# schematic.net
KiCad netlist of a schematic drawn in Altium Designer
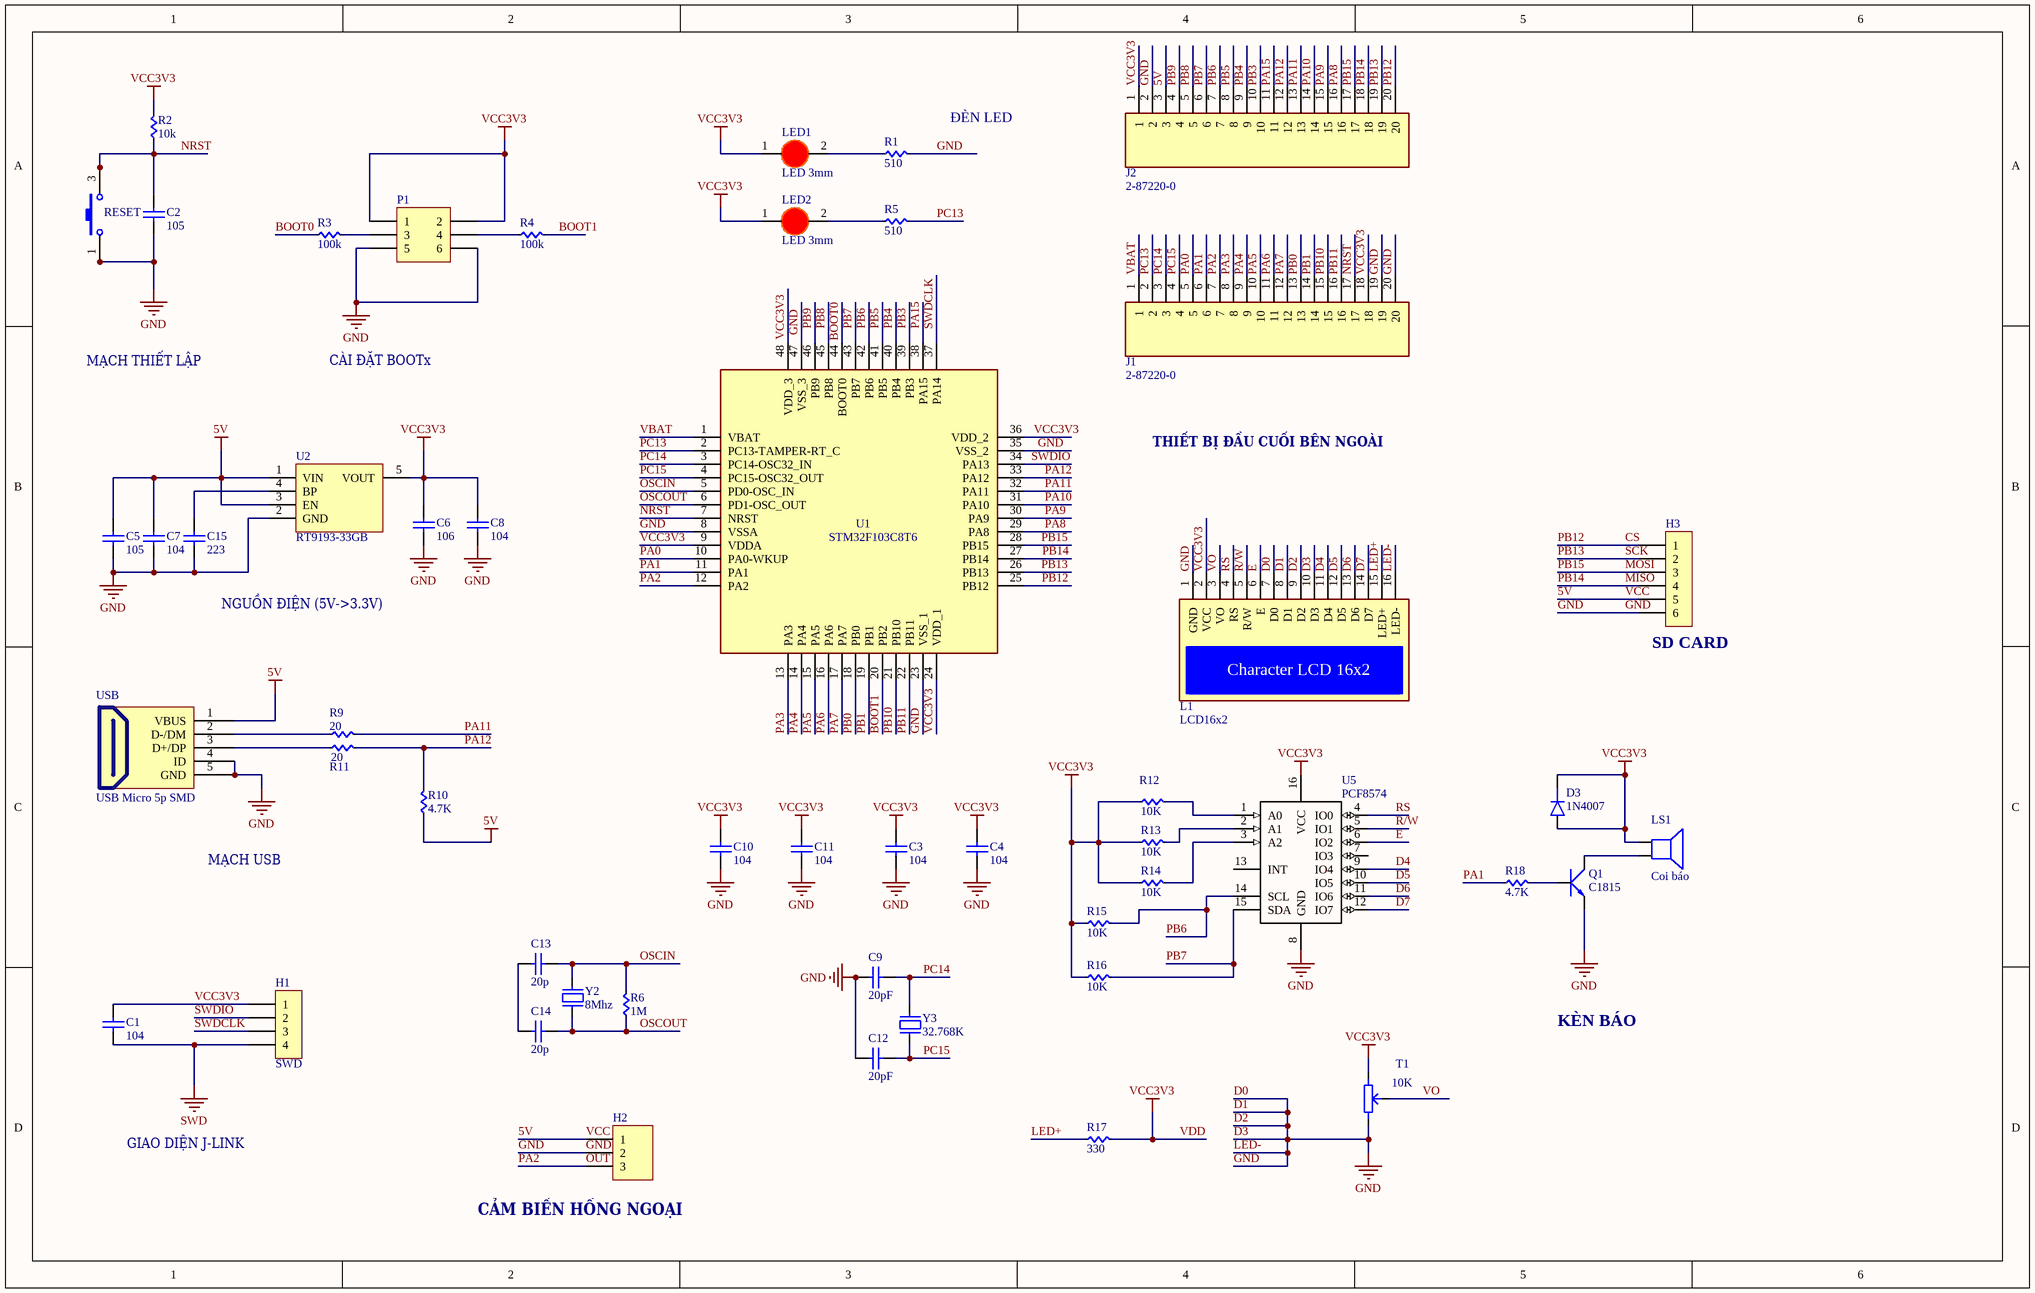
[diagram p0: schematic.SchDoc]

(export (version "E")
  (design (tool "Eeschema 10.0.6"))
  (components
    (comp (ref "C1")
      (value "104")
      (footprint "tu 0603")
      (description "Dán")
      (libsource (lib "") (part "Tu 0402 220nF 6.3V 20%_1"))
    )
    (comp (ref "C2")
      (value "105")
      (footprint "tu 0603")
      (description "Dán")
      (libsource (lib "") (part "Tu 0402 220nF 6.3V 20%_1"))
    )
    (comp (ref "C3")
      (value "104")
      (footprint "tu 0603")
      (description "Dán")
      (libsource (lib "Altium_Lib_by_KhueNguyenCreator") (part "Tu 0603 104 50V 10%"))
    )
    (comp (ref "C4")
      (value "104")
      (footprint "tu 0603")
      (description "Dán")
      (libsource (lib "Altium_Lib_by_KhueNguyenCreator") (part "Tu 0603 104 50V 10%"))
    )
    (comp (ref "C5")
      (value "105")
      (footprint "tu 0603")
      (description "Dán")
      (libsource (lib "") (part "Tu 0402 220nF 6.3V 20%_1"))
    )
    (comp (ref "C6")
      (value "106")
      (footprint "tu 0603")
      (description "Dán")
      (libsource (lib "Altium_Lib_by_KhueNguyenCreator") (part "Tu 0402 220nF 6.3V 20%"))
    )
    (comp (ref "C7")
      (value "104")
      (footprint "tu 0603")
      (description "Dán")
      (libsource (lib "Altium_Lib_by_KhueNguyenCreator") (part "Tu 0402 220nF 6.3V 20%"))
    )
    (comp (ref "C8")
      (value "104")
      (footprint "tu 0603")
      (description "Dán")
      (libsource (lib "Altium_Lib_by_KhueNguyenCreator") (part "Tu 0402 220nF 6.3V 20%"))
    )
    (comp (ref "C9")
      (value "20pF")
      (footprint "tu 0805")
      (description "Dán")
      (libsource (lib "Altium_Lib_by_KhueNguyenCreator") (part "Tu 0402 220nF 6.3V 20%"))
    )
    (comp (ref "C10")
      (value "104")
      (footprint "tu 0603")
      (description "Dán")
      (libsource (lib "Altium_Lib_by_KhueNguyenCreator") (part "Tu 0603 104 50V 10%"))
    )
    (comp (ref "C11")
      (value "104")
      (footprint "tu 0603")
      (description "Dán")
      (libsource (lib "Altium_Lib_by_KhueNguyenCreator") (part "Tu 0603 104 50V 10%"))
    )
    (comp (ref "C12")
      (value "20pF")
      (footprint "tu 0805")
      (description "Dán")
      (libsource (lib "Altium_Lib_by_KhueNguyenCreator") (part "Tu 0402 220nF 6.3V 20%"))
    )
    (comp (ref "C13")
      (value "20p")
      (footprint "tu 0805")
      (description "Dán")
      (libsource (lib "Altium_Lib_by_KhueNguyenCreator") (part "Tu 0402 220nF 6.3V 20%"))
    )
    (comp (ref "C14")
      (value "20p")
      (footprint "tu 0805")
      (description "Dán")
      (libsource (lib "Altium_Lib_by_KhueNguyenCreator") (part "Tu 0402 220nF 6.3V 20%"))
    )
    (comp (ref "C15")
      (value "223")
      (footprint "tu 0603")
      (description "Dán")
      (libsource (lib "Altium_Lib_by_KhueNguyenCreator") (part "Tu 0402 220nF 6.3V 20%"))
    )
    (comp (ref "D3")
      (value "1N4007")
      (footprint "DO-214AC-2 (SMA)")
      (description "Diode SMD SMA (DO-214AA)")
      (libsource (lib "Schematic-Lib-PhilsLab") (part "D_SMA"))
    )
    (comp (ref "H1")
      (value "SWD")
      (footprint "XH2.54M-4")
      (description "Cắm")
      (libsource (lib "Altium_Lib_by_KhueNguyenCreator") (part "Header 4P 2.54 Duc Thang"))
    )
    (comp (ref "H2")
      (value "Header 3")
      (footprint "HDR1X3")
      (description "Header, 3-Pin")
      (fields (field (name "PUBLISHER") "Altium Limited"))
      (libsource (lib "KhanhBK_SCH_Library_2") (part "Header 3"))
    )
    (comp (ref "H3")
      (value "Header 6P 2.54 Duc Thang")
      (footprint "XH2.54M-6")
      (description "Cắm")
      (libsource (lib "Altium_Lib_by_KhueNguyenCreator") (part "Header 6P 2.54 Duc Thang"))
    )
    (comp (ref "J1")
      (value "2-87220-0")
      (footprint "TE_2-87220-0")
      (fields (field (name "MF") "TE Connectivity"))
      (libsource (lib "2-87220-0") (part "2-87220-0"))
    )
    (comp (ref "J2")
      (value "2-87220-0")
      (footprint "TE_2-87220-0")
      (fields (field (name "MF") "TE Connectivity"))
      (libsource (lib "2-87220-0") (part "2-87220-0"))
    )
    (comp (ref "L1")
      (value "LCD16x2")
      (footprint "LCD16X2_3 HOLES")
      (description "Character LCD 16x2")
      (libsource (lib "KhanhBK_SCH_Lib_5") (part "LCD16x2"))
    )
    (comp (ref "LED1")
      (value "LED 3mm")
      (footprint "LED-3MM-RED")
      (description "Cắm")
      (libsource (lib "Altium_Lib_by_KhueNguyenCreator") (part "LED 3mm Do"))
    )
    (comp (ref "LED2")
      (value "LED 3mm")
      (footprint "LED-3MM-RED")
      (description "Cắm")
      (libsource (lib "Altium_Lib_by_KhueNguyenCreator") (part "LED 3mm Do"))
    )
    (comp (ref "LS1")
      (value "Coi báo")
      (footprint "Coi Chip Speacker")
      (description "Còi chip")
      (libsource (lib "Altium_Lib_by_KhueNguyenCreator") (part "Coi Chip Speaker"))
    )
    (comp (ref "P1")
      (value "95278-101A06LF")
      (footprint "HDR_M_2X3_2.54_SMD")
      (description "BERGSTIK HDR 6POS .100\" DR SMT")
      (fields (field (name "MANUFACTURER") "Amphenol FCI"))
      (libsource (lib "KhanhBK_SCH_Lib_6") (part "HDR_M_95278-101A06LF"))
    )
    (comp (ref "Q1")
      (value "C1815")
      (footprint "TO92")
      (description "NPN transistor")
      (libsource (lib "Altium_Lib_by_KhueNguyenCreator") (part "Trans C1815 DIP"))
    )
    (comp (ref "R1")
      (value "510")
      (footprint "RES 0402")
      (description "RES SMD 0402")
      (fields
        (field (name "MANUFACTURER") "Vishay Dale")
        (field (name "MANUFACTURER PART NUMBER") "CRCW040210K0FKED")
      )
      (libsource (lib "Altium_Lib_by_KhueNguyenCreator") (part "RES 0402"))
    )
    (comp (ref "R2")
      (value "10k")
      (footprint "RES 0402")
      (description "RES SMD 0402")
      (fields
        (field (name "MANUFACTURER") "Vishay Dale")
        (field (name "MANUFACTURER PART NUMBER") "CRCW040210K0FKED")
      )
      (libsource (lib "Altium_Lib_by_KhueNguyenCreator") (part "RES 0402"))
    )
    (comp (ref "R3")
      (value "100k")
      (footprint "RES 0402")
      (description "RES SMD 0402")
      (fields
        (field (name "MANUFACTURER") "Vishay Dale")
        (field (name "MANUFACTURER PART NUMBER") "CRCW040210K0FKED")
      )
      (libsource (lib "Altium_Lib_by_KhueNguyenCreator") (part "RES 0402"))
    )
    (comp (ref "R4")
      (value "100k")
      (footprint "RES 0402")
      (description "RES SMD 0402")
      (fields
        (field (name "MANUFACTURER") "Vishay Dale")
        (field (name "MANUFACTURER PART NUMBER") "CRCW040210K0FKED")
      )
      (libsource (lib "Altium_Lib_by_KhueNguyenCreator") (part "RES 0402"))
    )
    (comp (ref "R5")
      (value "510")
      (footprint "RES 0402")
      (description "RES SMD 0402")
      (fields
        (field (name "MANUFACTURER") "Vishay Dale")
        (field (name "MANUFACTURER PART NUMBER") "CRCW040210K0FKED")
      )
      (libsource (lib "Altium_Lib_by_KhueNguyenCreator") (part "RES 0402"))
    )
    (comp (ref "R6")
      (value "1M")
      (footprint "RES 0402")
      (description "RES SMD 0402")
      (fields
        (field (name "MANUFACTURER") "Vishay Dale")
        (field (name "MANUFACTURER PART NUMBER") "CRCW040210K0FKED")
      )
      (libsource (lib "Altium_Lib_by_KhueNguyenCreator") (part "RES 0402"))
    )
    (comp (ref "R9")
      (value "20")
      (footprint "RES 0402")
      (description "RES SMD 0402")
      (fields
        (field (name "MANUFACTURER") "Vishay Dale")
        (field (name "MANUFACTURER PART NUMBER") "CRCW040210K0FKED")
      )
      (libsource (lib "Altium_Lib_by_KhueNguyenCreator") (part "RES 0402"))
    )
    (comp (ref "R10")
      (value "4.7K")
      (footprint "RES 0402")
      (description "RES SMD 0402")
      (fields
        (field (name "MANUFACTURER") "Vishay Dale")
        (field (name "MANUFACTURER PART NUMBER") "CRCW040210K0FKED")
      )
      (libsource (lib "Altium_Lib_by_KhueNguyenCreator") (part "RES 0402"))
    )
    (comp (ref "R11")
      (value "20")
      (footprint "RES 0402")
      (description "RES SMD 0402")
      (fields
        (field (name "MANUFACTURER") "Vishay Dale")
        (field (name "MANUFACTURER PART NUMBER") "CRCW040210K0FKED")
      )
      (libsource (lib "Altium_Lib_by_KhueNguyenCreator") (part "RES 0402"))
    )
    (comp (ref "R12")
      (value "10K")
      (footprint "RES 0402")
      (description "RES SMD 0402")
      (fields
        (field (name "MANUFACTURER") "Vishay Dale")
        (field (name "MANUFACTURER PART NUMBER") "CRCW040210K0FKED")
      )
      (libsource (lib "Altium_Lib_by_KhueNguyenCreator") (part "RES 0402"))
    )
    (comp (ref "R13")
      (value "10K")
      (footprint "RES 0402")
      (description "RES SMD 0402")
      (fields
        (field (name "MANUFACTURER") "Vishay Dale")
        (field (name "MANUFACTURER PART NUMBER") "CRCW040210K0FKED")
      )
      (libsource (lib "Altium_Lib_by_KhueNguyenCreator") (part "RES 0402"))
    )
    (comp (ref "R14")
      (value "10K")
      (footprint "RES 0402")
      (description "RES SMD 0402")
      (fields
        (field (name "MANUFACTURER") "Vishay Dale")
        (field (name "MANUFACTURER PART NUMBER") "CRCW040210K0FKED")
      )
      (libsource (lib "Altium_Lib_by_KhueNguyenCreator") (part "RES 0402"))
    )
    (comp (ref "R15")
      (value "10K")
      (footprint "RES 0402")
      (description "RES SMD 0402")
      (fields
        (field (name "MANUFACTURER") "Vishay Dale")
        (field (name "MANUFACTURER PART NUMBER") "CRCW040210K0FKED")
      )
      (libsource (lib "Altium_Lib_by_KhueNguyenCreator") (part "RES 0402"))
    )
    (comp (ref "R16")
      (value "10K")
      (footprint "RES 0402")
      (description "RES SMD 0402")
      (fields
        (field (name "MANUFACTURER") "Vishay Dale")
        (field (name "MANUFACTURER PART NUMBER") "CRCW040210K0FKED")
      )
      (libsource (lib "Altium_Lib_by_KhueNguyenCreator") (part "RES 0402"))
    )
    (comp (ref "R17")
      (value "330")
      (footprint "RES 0402")
      (description "RES SMD 0402")
      (fields
        (field (name "MANUFACTURER") "Vishay Dale")
        (field (name "MANUFACTURER PART NUMBER") "CRCW040210K0FKED")
      )
      (libsource (lib "Altium_Lib_by_KhueNguyenCreator") (part "RES 0402"))
    )
    (comp (ref "R18")
      (value "4.7K")
      (footprint "RES 0402")
      (description "RES SMD 0402")
      (fields
        (field (name "MANUFACTURER") "Vishay Dale")
        (field (name "MANUFACTURER PART NUMBER") "CRCW040210K0FKED")
      )
      (libsource (lib "Altium_Lib_by_KhueNguyenCreator") (part "RES 0402"))
    )
    (comp (ref "RESET")
      (value "5ESH935")
      (footprint "SW_5ESH935")
      (description "SWITCH TACTILE SPST-NO 0.05A 24V")
      (libsource (lib "KhanhBK_SCH_Lib_6") (part "SW_5ESH935"))
    )
    (comp (ref "T1")
      (value "10K")
      (footprint "Bien Tro Tam Giac Dung")
      (description "Cắm")
      (libsource (lib "Altium_Lib_by_KhueNguyenCreator") (part "Bien tro tam giac 100K Dung"))
    )
    (comp (ref "U1")
      (value "STM32F103C8T6")
      (footprint "LQFP-48_19.6_393_58X11_SMD")
      (description "ARM® Cortex®-M3 STM32F1 Microcontroller IC 32-Bit 72MHz 64KB (64K x 8) FLASH 48-LQFP (7x7)")
      (fields (field (name "MANUFACTURER") "STMicroelectronics"))
      (libsource (lib "Altium_Lib_by_KhueNguyenCreator") (part "IC_STM32F103C8T6"))
    )
    (comp (ref "U2")
      (value "RT9193-33GB")
      (footprint "SOT23-5")
      (description "Linear Voltage Regulator IC 1 Output 300mA SOT-23-5")
      (fields (field (name "MANUFACTURER") "Richtek USA Inc."))
      (libsource (lib "Altium_Lib_by_KhueNguyenCreator") (part "REG_5.5V-3.3V-0.3A-1W-SOT-23-5"))
    )
    (comp (ref "U5")
      (value "PCF8574")
      (footprint "DIP16")
      (description "I2C PORT EXPANDER")
      (fields
        (field (name "MANUFACTURER PART NUMBER") "PCF8574T/3,512")
        (field (name "MANUFACTURER") "NXP Semiconductors")
      )
      (libsource (lib "KhanhBK_SCH_Library_2") (part "PCF8574"))
    )
    (comp (ref "USB")
      (value "USB Micro 5p SMD")
      (footprint "USB Micro 5p SMD")
      (description "USB Type B")
      (libsource (lib "Altium_Lib_by_KhueNguyenCreator") (part "USB Micro 5p SMD"))
    )
    (comp (ref "Y2")
      (value "8Mhz")
      (footprint "Thach Anh 2 chan SMD5032")
      (description "Crystal For all Crystal 2pin.")
      (libsource (lib "Altium_Lib_by_KhueNguyenCreator") (part "Thach Anh 2 chan SMD 5032"))
    )
    (comp (ref "Y3")
      (value "32.768K")
      (footprint "Thach Anh 2 chan SMD5032")
      (description "Crystal For all Crystal 2pin.")
      (libsource (lib "Altium_Lib_by_KhueNguyenCreator") (part "Thach Anh 2 chan SMD 5032"))
    )
  )
  (nets
    (net (code "1") (name "/BOOT0") (class "Default")
      (node (ref "R3") (pin "1") (pinfunction "1_1") (pintype "passive"))
      (node (ref "U1") (pin "44") (pinfunction "BOOT0_44") (pintype "passive"))
    )
    (net (code "2") (name "/BOOT1") (class "Default")
      (node (ref "R4") (pin "2") (pinfunction "2_2") (pintype "passive"))
      (node (ref "U1") (pin "20") (pinfunction "PB2_20") (pintype "passive"))
    )
    (net (code "3") (name "/CS") (class "Default")
      (node (ref "H3") (pin "1") (pinfunction "1_1") (pintype "passive"))
      (node (ref "J2") (pin "20") (pinfunction "20_20") (pintype "passive"))
      (node (ref "U1") (pin "25") (pinfunction "PB12_25") (pintype "passive"))
    )
    (net (code "4") (name "/D4") (class "Default")
      (node (ref "L1") (pin "11") (pinfunction "D4_11") (pintype "passive"))
      (node (ref "U5") (pin "9") (pinfunction "IO4_9") (pintype "bidirectional"))
    )
    (net (code "5") (name "/D5") (class "Default")
      (node (ref "L1") (pin "12") (pinfunction "D5_12") (pintype "passive"))
      (node (ref "U5") (pin "10") (pinfunction "IO5_10") (pintype "bidirectional"))
    )
    (net (code "6") (name "/D6") (class "Default")
      (node (ref "L1") (pin "13") (pinfunction "D6_13") (pintype "passive"))
      (node (ref "U5") (pin "11") (pinfunction "IO6_11") (pintype "bidirectional"))
    )
    (net (code "7") (name "/D7") (class "Default")
      (node (ref "L1") (pin "14") (pinfunction "D7_14") (pintype "passive"))
      (node (ref "U5") (pin "12") (pinfunction "IO7_12") (pintype "bidirectional"))
    )
    (net (code "8") (name "/E") (class "Default")
      (node (ref "L1") (pin "6") (pinfunction "E_6") (pintype "passive"))
      (node (ref "U5") (pin "6") (pinfunction "IO2_6") (pintype "bidirectional"))
    )
    (net (code "9") (name "/LED+") (class "Default")
      (node (ref "L1") (pin "15") (pinfunction "LED+_15") (pintype "passive"))
      (node (ref "R17") (pin "1") (pinfunction "1_1") (pintype "passive"))
    )
    (net (code "10") (name "/MISO") (class "Default")
      (node (ref "H3") (pin "4") (pinfunction "4_4") (pintype "passive"))
      (node (ref "J2") (pin "18") (pinfunction "18_18") (pintype "passive"))
      (node (ref "U1") (pin "27") (pinfunction "PB14_27") (pintype "passive"))
    )
    (net (code "11") (name "/MOSI") (class "Default")
      (node (ref "H3") (pin "3") (pinfunction "3_3") (pintype "passive"))
      (node (ref "J2") (pin "17") (pinfunction "17_17") (pintype "passive"))
      (node (ref "U1") (pin "28") (pinfunction "PB15_28") (pintype "passive"))
    )
    (net (code "12") (name "/NRST") (class "Default")
      (node (ref "C2") (pin "1") (pinfunction "1_1") (pintype "passive"))
      (node (ref "J1") (pin "17") (pinfunction "17_17") (pintype "passive"))
      (node (ref "R2") (pin "1") (pinfunction "1_1") (pintype "passive"))
      (node (ref "RESET") (pin "3") (pinfunction "UP_3") (pintype "passive"))
      (node (ref "RESET") (pin "4") (pinfunction "DOWN_4") (pintype "passive"))
      (node (ref "U1") (pin "7") (pinfunction "NRST_7") (pintype "passive"))
    )
    (net (code "13") (name "/OSCIN") (class "Default")
      (node (ref "C13") (pin "1") (pinfunction "1_1") (pintype "passive"))
      (node (ref "R6") (pin "2") (pinfunction "2_2") (pintype "passive"))
      (node (ref "U1") (pin "5") (pinfunction "PD0-OSC_IN_5") (pintype "passive"))
      (node (ref "Y2") (pin "2") (pinfunction "2_2") (pintype "passive"))
    )
    (net (code "14") (name "/OSCOUT") (class "Default")
      (node (ref "C14") (pin "1") (pinfunction "1_1") (pintype "passive"))
      (node (ref "R6") (pin "1") (pinfunction "1_1") (pintype "passive"))
      (node (ref "U1") (pin "6") (pinfunction "PD1-OSC_OUT_6") (pintype "passive"))
      (node (ref "Y2") (pin "1") (pinfunction "1_1") (pintype "passive"))
    )
    (net (code "15") (name "/OUT") (class "Default")
      (node (ref "H2") (pin "3") (pinfunction "3_3") (pintype "passive"))
      (node (ref "J1") (pin "7") (pinfunction "7_7") (pintype "passive"))
      (node (ref "U1") (pin "12") (pinfunction "PA2_12") (pintype "passive"))
    )
    (net (code "16") (name "/PA0") (class "Default")
      (node (ref "J1") (pin "5") (pinfunction "5_5") (pintype "passive"))
      (node (ref "U1") (pin "10") (pinfunction "PA0-WKUP_10") (pintype "passive"))
    )
    (net (code "17") (name "/PA1") (class "Default")
      (node (ref "J1") (pin "6") (pinfunction "6_6") (pintype "passive"))
      (node (ref "R18") (pin "1") (pinfunction "1_1") (pintype "passive"))
      (node (ref "U1") (pin "11") (pinfunction "PA1_11") (pintype "passive"))
    )
    (net (code "18") (name "/PA3") (class "Default")
      (node (ref "J1") (pin "8") (pinfunction "8_8") (pintype "passive"))
      (node (ref "U1") (pin "13") (pinfunction "PA3_13") (pintype "passive"))
    )
    (net (code "19") (name "/PA4") (class "Default")
      (node (ref "J1") (pin "9") (pinfunction "9_9") (pintype "passive"))
      (node (ref "U1") (pin "14") (pinfunction "PA4_14") (pintype "passive"))
    )
    (net (code "20") (name "/PA5") (class "Default")
      (node (ref "J1") (pin "10") (pinfunction "10_10") (pintype "passive"))
      (node (ref "U1") (pin "15") (pinfunction "PA5_15") (pintype "passive"))
    )
    (net (code "21") (name "/PA6") (class "Default")
      (node (ref "J1") (pin "11") (pinfunction "11_11") (pintype "passive"))
      (node (ref "U1") (pin "16") (pinfunction "PA6_16") (pintype "passive"))
    )
    (net (code "22") (name "/PA7") (class "Default")
      (node (ref "J1") (pin "12") (pinfunction "12_12") (pintype "passive"))
      (node (ref "U1") (pin "17") (pinfunction "PA7_17") (pintype "passive"))
    )
    (net (code "23") (name "/PA8") (class "Default")
      (node (ref "J2") (pin "16") (pinfunction "16_16") (pintype "passive"))
      (node (ref "U1") (pin "29") (pinfunction "PA8_29") (pintype "passive"))
    )
    (net (code "24") (name "/PA9") (class "Default")
      (node (ref "J2") (pin "15") (pinfunction "15_15") (pintype "passive"))
      (node (ref "U1") (pin "30") (pinfunction "PA9_30") (pintype "passive"))
    )
    (net (code "25") (name "/PA10") (class "Default")
      (node (ref "J2") (pin "14") (pinfunction "14_14") (pintype "passive"))
      (node (ref "U1") (pin "31") (pinfunction "PA10_31") (pintype "passive"))
    )
    (net (code "26") (name "/PA11") (class "Default")
      (node (ref "J2") (pin "13") (pinfunction "13_13") (pintype "passive"))
      (node (ref "R9") (pin "2") (pinfunction "2_2") (pintype "passive"))
      (node (ref "U1") (pin "32") (pinfunction "PA11_32") (pintype "passive"))
    )
    (net (code "27") (name "/PA12") (class "Default")
      (node (ref "J2") (pin "12") (pinfunction "12_12") (pintype "passive"))
      (node (ref "R10") (pin "2") (pinfunction "2_2") (pintype "passive"))
      (node (ref "R11") (pin "2") (pinfunction "2_2") (pintype "passive"))
      (node (ref "U1") (pin "33") (pinfunction "PA12_33") (pintype "passive"))
    )
    (net (code "28") (name "/PA15") (class "Default")
      (node (ref "J2") (pin "11") (pinfunction "11_11") (pintype "passive"))
      (node (ref "U1") (pin "38") (pinfunction "PA15_38") (pintype "passive"))
    )
    (net (code "29") (name "/PB0") (class "Default")
      (node (ref "J1") (pin "13") (pinfunction "13_13") (pintype "passive"))
      (node (ref "U1") (pin "18") (pinfunction "PB0_18") (pintype "passive"))
    )
    (net (code "30") (name "/PB1") (class "Default")
      (node (ref "J1") (pin "14") (pinfunction "14_14") (pintype "passive"))
      (node (ref "U1") (pin "19") (pinfunction "PB1_19") (pintype "passive"))
    )
    (net (code "31") (name "/PB3") (class "Default")
      (node (ref "J2") (pin "10") (pinfunction "10_10") (pintype "passive"))
      (node (ref "U1") (pin "39") (pinfunction "PB3_39") (pintype "passive"))
    )
    (net (code "32") (name "/PB4") (class "Default")
      (node (ref "J2") (pin "9") (pinfunction "9_9") (pintype "passive"))
      (node (ref "U1") (pin "40") (pinfunction "PB4_40") (pintype "passive"))
    )
    (net (code "33") (name "/PB5") (class "Default")
      (node (ref "J2") (pin "8") (pinfunction "8_8") (pintype "passive"))
      (node (ref "U1") (pin "41") (pinfunction "PB5_41") (pintype "passive"))
    )
    (net (code "34") (name "/PB6") (class "Default")
      (node (ref "J2") (pin "7") (pinfunction "7_7") (pintype "passive"))
      (node (ref "R15") (pin "2") (pinfunction "2_2") (pintype "passive"))
      (node (ref "U1") (pin "42") (pinfunction "PB6_42") (pintype "passive"))
      (node (ref "U5") (pin "14") (pinfunction "SCL_14") (pintype "open_collector"))
    )
    (net (code "35") (name "/PB7") (class "Default")
      (node (ref "J2") (pin "6") (pinfunction "6_6") (pintype "passive"))
      (node (ref "R16") (pin "2") (pinfunction "2_2") (pintype "passive"))
      (node (ref "U1") (pin "43") (pinfunction "PB7_43") (pintype "passive"))
      (node (ref "U5") (pin "15") (pinfunction "SDA_15") (pintype "open_collector"))
    )
    (net (code "36") (name "/PB8") (class "Default")
      (node (ref "J2") (pin "5") (pinfunction "5_5") (pintype "passive"))
      (node (ref "U1") (pin "45") (pinfunction "PB8_45") (pintype "passive"))
    )
    (net (code "37") (name "/PB9") (class "Default")
      (node (ref "J2") (pin "4") (pinfunction "4_4") (pintype "passive"))
      (node (ref "U1") (pin "46") (pinfunction "PB9_46") (pintype "passive"))
    )
    (net (code "38") (name "/PB10") (class "Default")
      (node (ref "J1") (pin "15") (pinfunction "15_15") (pintype "passive"))
      (node (ref "U1") (pin "21") (pinfunction "PB10_21") (pintype "passive"))
    )
    (net (code "39") (name "/PB11") (class "Default")
      (node (ref "J1") (pin "16") (pinfunction "16_16") (pintype "passive"))
      (node (ref "U1") (pin "22") (pinfunction "PB11_22") (pintype "passive"))
    )
    (net (code "40") (name "/PB13") (class "Default")
      (node (ref "H3") (pin "2") (pinfunction "2_2") (pintype "passive"))
      (node (ref "J2") (pin "19") (pinfunction "19_19") (pintype "passive"))
      (node (ref "U1") (pin "26") (pinfunction "PB13_26") (pintype "passive"))
    )
    (net (code "41") (name "/PC13") (class "Default")
      (node (ref "J1") (pin "2") (pinfunction "2_2") (pintype "passive"))
      (node (ref "R5") (pin "2") (pinfunction "2_2") (pintype "passive"))
      (node (ref "U1") (pin "2") (pinfunction "PC13-TAMPER-RT_C_2") (pintype "passive"))
    )
    (net (code "42") (name "/PC14") (class "Default")
      (node (ref "C9") (pin "1") (pinfunction "1_1") (pintype "passive"))
      (node (ref "J1") (pin "3") (pinfunction "3_3") (pintype "passive"))
      (node (ref "U1") (pin "3") (pinfunction "PC14-OSC32_IN_3") (pintype "passive"))
      (node (ref "Y3") (pin "2") (pinfunction "2_2") (pintype "passive"))
    )
    (net (code "43") (name "/PC15") (class "Default")
      (node (ref "C12") (pin "1") (pinfunction "1_1") (pintype "passive"))
      (node (ref "J1") (pin "4") (pinfunction "4_4") (pintype "passive"))
      (node (ref "U1") (pin "4") (pinfunction "PC15-OSC32_OUT_4") (pintype "passive"))
      (node (ref "Y3") (pin "1") (pinfunction "1_1") (pintype "passive"))
    )
    (net (code "44") (name "/RS") (class "Default")
      (node (ref "L1") (pin "4") (pinfunction "RS_4") (pintype "passive"))
      (node (ref "U5") (pin "4") (pinfunction "IO0_4") (pintype "bidirectional"))
    )
    (net (code "45") (name "/R{slash}W") (class "Default")
      (node (ref "L1") (pin "5") (pinfunction "R/W_5") (pintype "passive"))
      (node (ref "U5") (pin "5") (pinfunction "IO1_5") (pintype "bidirectional"))
    )
    (net (code "46") (name "/SWDCLK") (class "Default")
      (node (ref "H1") (pin "3") (pinfunction "3_3") (pintype "passive"))
      (node (ref "U1") (pin "37") (pinfunction "PA14_37") (pintype "passive"))
    )
    (net (code "47") (name "/SWDIO") (class "Default")
      (node (ref "H1") (pin "2") (pinfunction "2_2") (pintype "passive"))
      (node (ref "U1") (pin "34") (pinfunction "PA13_34") (pintype "passive"))
    )
    (net (code "48") (name "/VBAT") (class "Default")
      (node (ref "J1") (pin "1") (pinfunction "1_1") (pintype "passive"))
      (node (ref "U1") (pin "1") (pinfunction "VBAT_1") (pintype "passive"))
    )
    (net (code "49") (name "/VO") (class "Default")
      (node (ref "L1") (pin "3") (pinfunction "VO_3") (pintype "passive"))
      (node (ref "T1") (pin "2") (pinfunction "2_2") (pintype "passive"))
    )
    (net (code "50") (name "5V") (class "Default")
      (node (ref "C5") (pin "1") (pinfunction "1_1") (pintype "passive"))
      (node (ref "C7") (pin "1") (pinfunction "1_1") (pintype "passive"))
      (node (ref "H2") (pin "1") (pinfunction "1_1") (pintype "passive"))
      (node (ref "H3") (pin "5") (pinfunction "5_5") (pintype "passive"))
      (node (ref "J2") (pin "3") (pinfunction "3_3") (pintype "passive"))
      (node (ref "R10") (pin "1") (pinfunction "1_1") (pintype "passive"))
      (node (ref "U2") (pin "1") (pinfunction "VIN_1") (pintype "passive"))
      (node (ref "U2") (pin "3") (pinfunction "EN_3") (pintype "passive"))
      (node (ref "USB") (pin "1") (pinfunction "VBUS_1") (pintype "passive"))
    )
    (net (code "51") (name "GND") (class "Default")
      (node (ref "C10") (pin "2") (pinfunction "2_2") (pintype "passive"))
      (node (ref "C11") (pin "2") (pinfunction "2_2") (pintype "passive"))
      (node (ref "C12") (pin "2") (pinfunction "2_2") (pintype "passive"))
      (node (ref "C15") (pin "2") (pinfunction "2_2") (pintype "passive"))
      (node (ref "C2") (pin "2") (pinfunction "2_2") (pintype "passive"))
      (node (ref "C3") (pin "2") (pinfunction "2_2") (pintype "passive"))
      (node (ref "C4") (pin "2") (pinfunction "2_2") (pintype "passive"))
      (node (ref "C5") (pin "2") (pinfunction "2_2") (pintype "passive"))
      (node (ref "C6") (pin "2") (pinfunction "2_2") (pintype "passive"))
      (node (ref "C7") (pin "2") (pinfunction "2_2") (pintype "passive"))
      (node (ref "C8") (pin "2") (pinfunction "2_2") (pintype "passive"))
      (node (ref "C9") (pin "2") (pinfunction "2_2") (pintype "passive"))
      (node (ref "H2") (pin "2") (pinfunction "2_2") (pintype "passive"))
      (node (ref "H3") (pin "6") (pinfunction "6_6") (pintype "passive"))
      (node (ref "J1") (pin "19") (pinfunction "19_19") (pintype "passive"))
      (node (ref "J1") (pin "20") (pinfunction "20_20") (pintype "passive"))
      (node (ref "J2") (pin "2") (pinfunction "2_2") (pintype "passive"))
      (node (ref "L1") (pin "1") (pinfunction "GND_1") (pintype "passive"))
      (node (ref "L1") (pin "10") (pinfunction "D3_10") (pintype "passive"))
      (node (ref "L1") (pin "16") (pinfunction "LED-_16") (pintype "passive"))
      (node (ref "L1") (pin "7") (pinfunction "D0_7") (pintype "passive"))
      (node (ref "L1") (pin "8") (pinfunction "D1_8") (pintype "passive"))
      (node (ref "L1") (pin "9") (pinfunction "D2_9") (pintype "passive"))
      (node (ref "P1") (pin "5") (pinfunction "5_5") (pintype "passive"))
      (node (ref "P1") (pin "6") (pinfunction "6_6") (pintype "passive"))
      (node (ref "Q1") (pin "1") (pinfunction "E_1") (pintype "passive"))
      (node (ref "R1") (pin "2") (pinfunction "2_2") (pintype "passive"))
      (node (ref "RESET") (pin "1") (pinfunction "C/M_1") (pintype "passive"))
      (node (ref "RESET") (pin "2") (pinfunction "C/M_2") (pintype "passive"))
      (node (ref "T1") (pin "3") (pinfunction "3_3") (pintype "passive"))
      (node (ref "U1") (pin "23") (pinfunction "VSS_1_23") (pintype "passive"))
      (node (ref "U1") (pin "35") (pinfunction "VSS_2_35") (pintype "passive"))
      (node (ref "U1") (pin "47") (pinfunction "VSS_3_47") (pintype "passive"))
      (node (ref "U1") (pin "8") (pinfunction "VSSA_8") (pintype "passive"))
      (node (ref "U2") (pin "2") (pinfunction "GND_2") (pintype "passive"))
      (node (ref "U5") (pin "8") (pinfunction "GND_8") (pintype "open_collector"))
      (node (ref "USB") (pin "4") (pinfunction "ID_4") (pintype "passive"))
      (node (ref "USB") (pin "5") (pinfunction "GND_5") (pintype "passive"))
    )
    (net (code "52") (name "Net-(C13-Pad2)") (class "Default")
      (node (ref "C13") (pin "2") (pinfunction "2_2") (pintype "passive"))
      (node (ref "C14") (pin "2") (pinfunction "2_2") (pintype "passive"))
    )
    (net (code "53") (name "Net-(LED1-K)") (class "Default")
      (node (ref "LED1") (pin "2") (pinfunction "K_2") (pintype "passive"))
      (node (ref "R1") (pin "1") (pinfunction "1_1") (pintype "passive"))
    )
    (net (code "54") (name "Net-(LED2-K)") (class "Default")
      (node (ref "LED2") (pin "2") (pinfunction "K_2") (pintype "passive"))
      (node (ref "R5") (pin "1") (pinfunction "1_1") (pintype "passive"))
    )
    (net (code "55") (name "Net-(P1-Pad3)") (class "Default")
      (node (ref "P1") (pin "3") (pinfunction "3_3") (pintype "passive"))
      (node (ref "R3") (pin "2") (pinfunction "2_2") (pintype "passive"))
    )
    (net (code "56") (name "Net-(P1-Pad4)") (class "Default")
      (node (ref "P1") (pin "4") (pinfunction "4_4") (pintype "passive"))
      (node (ref "R4") (pin "1") (pinfunction "1_1") (pintype "passive"))
    )
    (net (code "57") (name "Net-(Q1-B)") (class "Default")
      (node (ref "Q1") (pin "3") (pinfunction "B_3") (pintype "passive"))
      (node (ref "R18") (pin "2") (pinfunction "2_2") (pintype "passive"))
    )
    (net (code "58") (name "Net-(Q1-C)") (class "Default")
      (node (ref "LS1") (pin "2") (pinfunction "2_2") (pintype "passive"))
      (node (ref "Q1") (pin "2") (pinfunction "C_2") (pintype "passive"))
    )
    (net (code "59") (name "Net-(U2-BP)") (class "Default")
      (node (ref "C15") (pin "1") (pinfunction "1_1") (pintype "passive"))
      (node (ref "U2") (pin "4") (pinfunction "BP_4") (pintype "passive"))
    )
    (net (code "60") (name "Net-(U5-A0)") (class "Default")
      (node (ref "R12") (pin "2") (pinfunction "2_2") (pintype "passive"))
      (node (ref "U5") (pin "1") (pinfunction "A0_1") (pintype "input"))
    )
    (net (code "61") (name "Net-(U5-A1)") (class "Default")
      (node (ref "R13") (pin "2") (pinfunction "2_2") (pintype "passive"))
      (node (ref "U5") (pin "2") (pinfunction "A1_2") (pintype "input"))
    )
    (net (code "62") (name "Net-(U5-A2)") (class "Default")
      (node (ref "R14") (pin "2") (pinfunction "2_2") (pintype "passive"))
      (node (ref "U5") (pin "3") (pinfunction "A2_3") (pintype "input"))
    )
    (net (code "63") (name "Net-(USB-D+{slash}DP)") (class "Default")
      (node (ref "R11") (pin "1") (pinfunction "1_1") (pintype "passive"))
      (node (ref "USB") (pin "3") (pinfunction "D+/DP_3") (pintype "passive"))
    )
    (net (code "64") (name "Net-(USB-D-{slash}DM)") (class "Default")
      (node (ref "R9") (pin "1") (pinfunction "1_1") (pintype "passive"))
      (node (ref "USB") (pin "2") (pinfunction "D-/DM_2") (pintype "passive"))
    )
    (net (code "65") (name "SWD") (class "Default")
      (node (ref "C1") (pin "2") (pinfunction "2_2") (pintype "passive"))
      (node (ref "H1") (pin "4") (pinfunction "4_4") (pintype "passive"))
    )
    (net (code "66") (name "VCC3V3") (class "Default")
      (node (ref "C1") (pin "1") (pinfunction "1_1") (pintype "passive"))
      (node (ref "C10") (pin "1") (pinfunction "1_1") (pintype "passive"))
      (node (ref "C11") (pin "1") (pinfunction "1_1") (pintype "passive"))
      (node (ref "C3") (pin "1") (pinfunction "1_1") (pintype "passive"))
      (node (ref "C4") (pin "1") (pinfunction "1_1") (pintype "passive"))
      (node (ref "C6") (pin "1") (pinfunction "1_1") (pintype "passive"))
      (node (ref "C8") (pin "1") (pinfunction "1_1") (pintype "passive"))
      (node (ref "D3") (pin "A") (pinfunction "A_A") (pintype "passive"))
      (node (ref "D3") (pin "K") (pinfunction "K_K") (pintype "passive"))
      (node (ref "H1") (pin "1") (pinfunction "1_1") (pintype "passive"))
      (node (ref "J1") (pin "18") (pinfunction "18_18") (pintype "passive"))
      (node (ref "J2") (pin "1") (pinfunction "1_1") (pintype "passive"))
      (node (ref "L1") (pin "2") (pinfunction "VCC_2") (pintype "passive"))
      (node (ref "LED1") (pin "1") (pinfunction "A_1") (pintype "passive"))
      (node (ref "LED2") (pin "1") (pinfunction "A_1") (pintype "passive"))
      (node (ref "LS1") (pin "1") (pinfunction "1_1") (pintype "passive"))
      (node (ref "P1") (pin "1") (pinfunction "1_1") (pintype "passive"))
      (node (ref "P1") (pin "2") (pinfunction "2_2") (pintype "passive"))
      (node (ref "R12") (pin "1") (pinfunction "1_1") (pintype "passive"))
      (node (ref "R13") (pin "1") (pinfunction "1_1") (pintype "passive"))
      (node (ref "R14") (pin "1") (pinfunction "1_1") (pintype "passive"))
      (node (ref "R15") (pin "1") (pinfunction "1_1") (pintype "passive"))
      (node (ref "R16") (pin "1") (pinfunction "1_1") (pintype "passive"))
      (node (ref "R17") (pin "2") (pinfunction "2_2") (pintype "passive"))
      (node (ref "R2") (pin "2") (pinfunction "2_2") (pintype "passive"))
      (node (ref "T1") (pin "1") (pinfunction "1_1") (pintype "passive"))
      (node (ref "U1") (pin "24") (pinfunction "VDD_1_24") (pintype "passive"))
      (node (ref "U1") (pin "36") (pinfunction "VDD_2_36") (pintype "passive"))
      (node (ref "U1") (pin "48") (pinfunction "VDD_3_48") (pintype "passive"))
      (node (ref "U1") (pin "9") (pinfunction "VDDA_9") (pintype "passive"))
      (node (ref "U2") (pin "5") (pinfunction "VOUT_5") (pintype "passive"))
      (node (ref "U5") (pin "16") (pinfunction "VCC_16") (pintype "passive"))
    )
    (net (code "67") (name "unconnected-(U5-INT-Pad13)") (class "Default")
      (node (ref "U5") (pin "13") (pinfunction "INT_13") (pintype "open_collector"))
    )
    (net (code "68") (name "unconnected-(U5-IO3-Pad7)") (class "Default")
      (node (ref "U5") (pin "7") (pinfunction "IO3_7") (pintype "bidirectional"))
    )
  )
)
